# lv_controller.net
KiCad netlist of a schematic drawn in Altium Designer
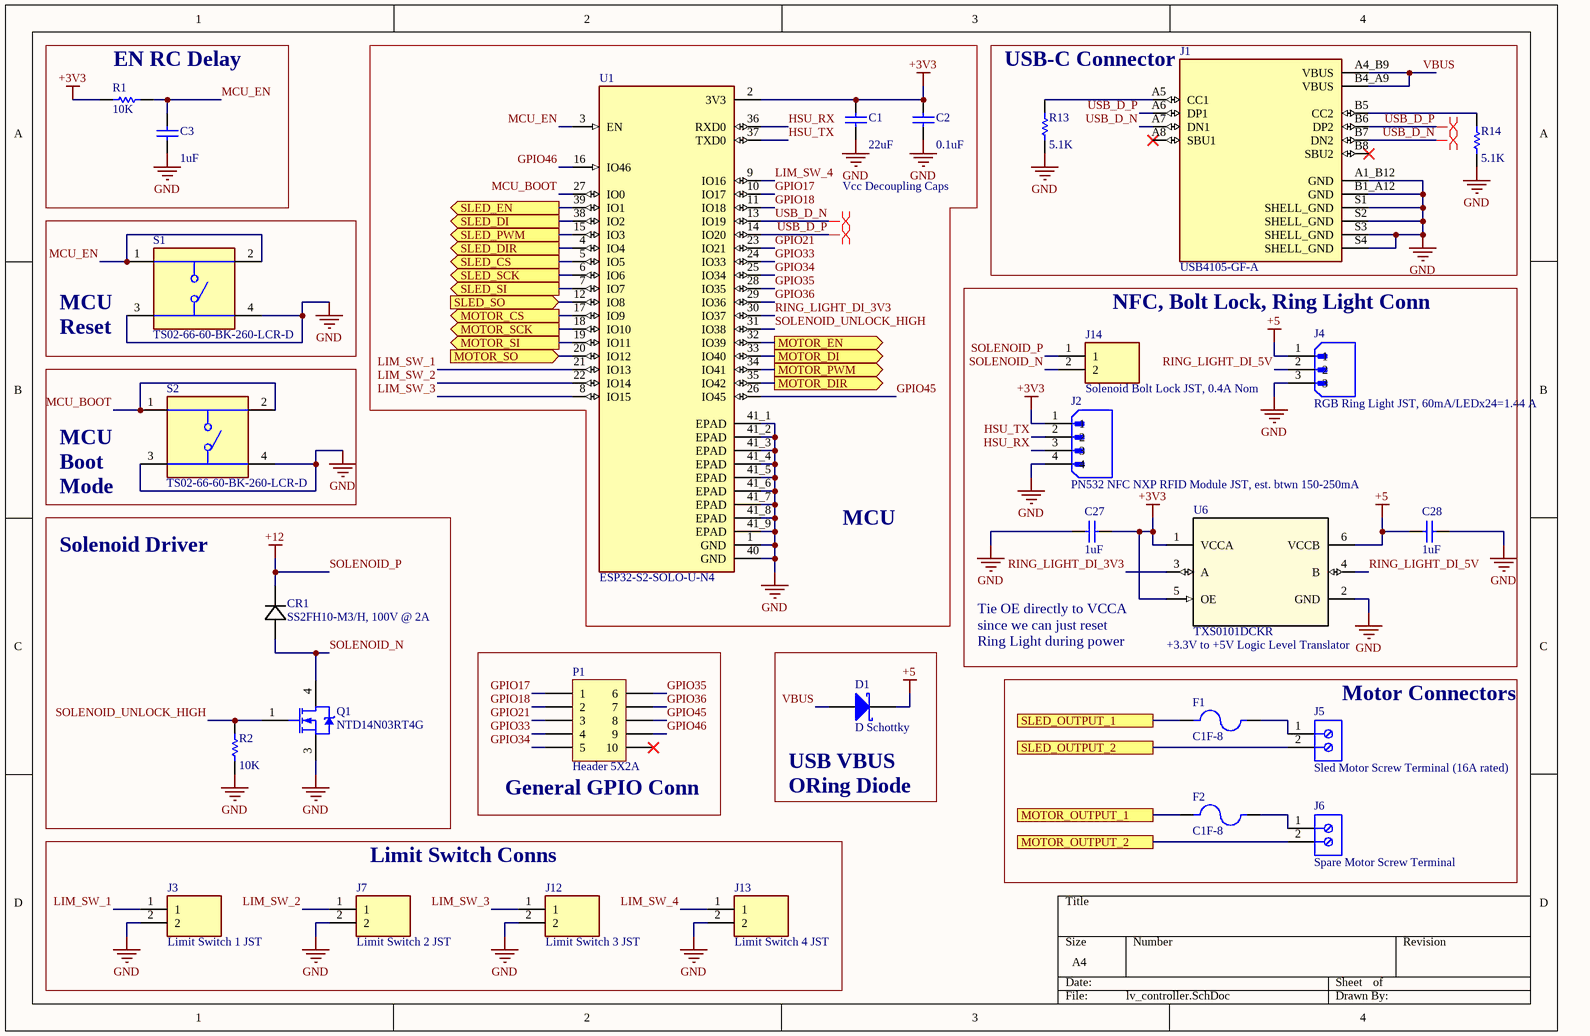
[diagram p0: lv_controller.SchDoc]

(export (version "E")
  (design (tool "Eeschema 10.0.6"))
  (components
    (comp (ref "C1")
      (value "22uF")
      (footprint "C0805")
      (description "Capacitor")
      (fields (field (name "Comment") "Cap") (field (name "PUBLISHER") "Altium Limited"))
      (libsource (lib "Miscellaneous Devices") (part "Cap"))
    )
    (comp (ref "C2")
      (value "0.1uF")
      (footprint "C0805")
      (description "Capacitor")
      (fields (field (name "Comment") "Cap") (field (name "PUBLISHER") "Altium Limited"))
      (libsource (lib "Miscellaneous Devices") (part "Cap"))
    )
    (comp (ref "C3")
      (value "1uF")
      (footprint "C0805")
      (description "Capacitor")
      (fields (field (name "Comment") "Cap") (field (name "PUBLISHER") "Altium Limited"))
      (libsource (lib "Miscellaneous Devices") (part "Cap"))
    )
    (comp (ref "C27")
      (value "1uF")
      (footprint "C0805")
      (description "Capacitor")
      (fields (field (name "Comment") "Cap") (field (name "PUBLISHER") "Altium Limited"))
      (libsource (lib "Miscellaneous Devices") (part "Cap"))
    )
    (comp (ref "C28")
      (value "1uF")
      (footprint "C0805")
      (description "Capacitor")
      (fields (field (name "Comment") "Cap") (field (name "PUBLISHER") "Altium Limited"))
      (libsource (lib "Miscellaneous Devices") (part "Cap"))
    )
    (comp (ref "CR1")
      (value "SS2FH10-M3/H, 100V @ 2A")
      (footprint "CR_10-M3/H_VIS")
      (description "No Description Available")
      (fields
        (field (name "MANUFACTURER_PART_NUMBER") "SS2FH10-M3/H")
        (field (name "COPYRIGHT") "Copyright (C) 2022 Ultra Librarian. All rights reserved.")
      )
      (libsource (lib "lv_controller_lib") (part "SS2FH10-M3/H"))
    )
    (comp (ref "D1")
      (value "D Schottky")
      (footprint "SODFL4725X110N:SODFL4725X110N")
      (description "Schottky Diode")
      (fields (field (name "PUBLISHER") "Altium Limited"))
      (libsource (lib "Miscellaneous Devices") (part "D Schottky"))
    )
    (comp (ref "F1")
      (value "C1F-8")
      (footprint "FUSC3215X83N")
      (description "C1F 8 (0685F8000-01) ¦ 1206 SMT Fuse ¦ Fast Acting ¦ 8A")
      (fields (field (name "MF") "Bel Fuse"))
      (libsource (lib "lv_controller_lib") (part "C1F-8"))
    )
    (comp (ref "F2")
      (value "C1F-8")
      (footprint "FUSC3215X83N")
      (description "C1F 8 (0685F8000-01) ¦ 1206 SMT Fuse ¦ Fast Acting ¦ 8A")
      (fields (field (name "MF") "Bel Fuse"))
      (libsource (lib "lv_controller_lib") (part "C1F-8"))
    )
    (comp (ref "J1")
      (value "USB4105-GF-A")
      (footprint "GCT_USB4105-GF-A")
      (fields (field (name "MF") "GCT"))
      (libsource (lib "lv_controller_lib") (part "USB4105-GF-A"))
    )
    (comp (ref "J2")
      (value "PN532 NFC NXP RFID Module JST, est. btwn 150-250mA")
      (footprint "JST_B4B-XH-A(LF)(SN)")
      (fields (field (name "MP") "B4B-XH-A(LF)(SN)"))
      (libsource (lib "lv_controller_lib") (part "B4B-XH-A(LF)(SN)"))
    )
    (comp (ref "J3")
      (value "Limit Switch 1 JST")
      (footprint "JST_B2B-XH-A(LF)(SN)")
      (description "Connector Header Through Hole 2 position 0.098 (2.50mm)")
      (fields (field (name "MP") "B2B-XH-A(LF)(SN)") (field (name "MF") "JST Sales"))
      (libsource (lib "lv_controller_lib") (part "B2B-XH-A(LF)(SN)"))
    )
    (comp (ref "J4")
      (value "RGB Ring Light JST, 60mA/LEDx24=1.44 A")
      (footprint "JST_B3B-XH-A(LF)(SN)")
      (fields (field (name "MP") "B3B-XH-A(LF)(SN)"))
      (libsource (lib "lv_controller_lib") (part "B3B-XH-A(LF)(SN)"))
    )
    (comp (ref "J5")
      (value "Sled Motor Screw Terminal (16A rated)")
      (footprint "PHOE-1725656-2")
      (description "Male Header, Pitch 2.54 mm, 1 x 2 Position, Height 9 mm, Tail Length 3.5 mm")
      (fields
        (field (name "MANUFACTURER PART NO.") "1725656")
        (field (name "MANUFACTURER") "Phoenix Contact")
      )
      (libsource (lib "Altium Content Vault") (part "CN-1P-F-TB2"))
    )
    (comp (ref "J6")
      (value "Spare Motor Screw Terminal")
      (footprint "PHOE-1725656-2")
      (description "Male Header, Pitch 2.54 mm, 1 x 2 Position, Height 9 mm, Tail Length 3.5 mm")
      (fields
        (field (name "MANUFACTURER PART NO.") "1725656")
        (field (name "MANUFACTURER") "Phoenix Contact")
      )
      (libsource (lib "Altium Content Vault") (part "CN-1P-F-TB2"))
    )
    (comp (ref "J7")
      (value "Limit Switch 2 JST")
      (footprint "JST_B2B-XH-A(LF)(SN)")
      (description "Connector Header Through Hole 2 position 0.098 (2.50mm)")
      (fields (field (name "MP") "B2B-XH-A(LF)(SN)") (field (name "MF") "JST Sales"))
      (libsource (lib "lv_controller_lib") (part "B2B-XH-A(LF)(SN)"))
    )
    (comp (ref "J12")
      (value "Limit Switch 3 JST")
      (footprint "JST_B2B-XH-A(LF)(SN)")
      (description "Connector Header Through Hole 2 position 0.098 (2.50mm)")
      (fields (field (name "MP") "B2B-XH-A(LF)(SN)") (field (name "MF") "JST Sales"))
      (libsource (lib "lv_controller_lib") (part "B2B-XH-A(LF)(SN)"))
    )
    (comp (ref "J13")
      (value "Limit Switch 4 JST")
      (footprint "JST_B2B-XH-A(LF)(SN)")
      (description "Connector Header Through Hole 2 position 0.098 (2.50mm)")
      (fields (field (name "MP") "B2B-XH-A(LF)(SN)") (field (name "MF") "JST Sales"))
      (libsource (lib "lv_controller_lib") (part "B2B-XH-A(LF)(SN)"))
    )
    (comp (ref "J14")
      (value "Solenoid Bolt Lock JST, 0.4A Nom")
      (footprint "JST_B2B-XH-A(LF)(SN)")
      (description "Connector Header Through Hole 2 position 0.098 (2.50mm)")
      (fields (field (name "MP") "B2B-XH-A(LF)(SN)") (field (name "MF") "JST Sales"))
      (libsource (lib "lv_controller_lib") (part "B2B-XH-A(LF)(SN)"))
    )
    (comp (ref "P1")
      (value "Header 5X2A")
      (footprint "HDR2X5_CEN")
      (description "Header, 5-Pin, Dual row")
      (fields (field (name "PUBLISHER") "Altium Limited"))
      (libsource (lib "Miscellaneous Connectors") (part "Header 5X2A"))
    )
    (comp (ref "Q1")
      (value "NTD14N03RT4G")
      (footprint "ONSC-DPAK-3-369C-01_V")
      (description "Power MOSFET, 14 A, 25 V, N-Channel, 3-Pin DPAK, Pb-Free, Tape and Reel")
      (fields (field (name "MANUFACTURER") "On Semiconductor"))
      (libsource (lib "Altium Content Vault") (part "ONSC-NMOS-G1S3D4-3_C"))
    )
    (comp (ref "R1")
      (value "10K")
      (footprint "6-0805_M")
      (description "Resistor")
      (fields (field (name "Comment") "Res1") (field (name "PUBLISHER") "Altium Limited"))
      (libsource (lib "Miscellaneous Devices") (part "Res1"))
    )
    (comp (ref "R2")
      (value "10K")
      (footprint "6-0805_M")
      (description "Resistor")
      (fields (field (name "Comment") "Res1") (field (name "PUBLISHER") "Altium Limited"))
      (libsource (lib "Miscellaneous Devices") (part "Res1"))
    )
    (comp (ref "R13")
      (value "5.1K")
      (footprint "6-0805_M")
      (description "Resistor")
      (fields (field (name "Comment") "Res1") (field (name "PUBLISHER") "Altium Limited"))
      (libsource (lib "Miscellaneous Devices") (part "Res1"))
    )
    (comp (ref "R14")
      (value "5.1K")
      (footprint "6-0805_M")
      (description "Resistor")
      (fields (field (name "Comment") "Res1") (field (name "PUBLISHER") "Altium Limited"))
      (libsource (lib "Miscellaneous Devices") (part "Res1"))
    )
    (comp (ref "S1")
      (value "TS02-66-60-BK-260-LCR-D")
      (footprint "SW_TS02-66-60-BK-260-LCR-D")
      (description "6 x 6 mm, 6 mm Actuator Height, 260 gf, Black, Long Crimped, Through Hole, SPST, Tactile Switch")
      (fields (field (name "MF") "CUI Devices"))
      (libsource (lib "lv_controller_lib") (part "TS02-66-60-BK-260-LCR-D"))
    )
    (comp (ref "S2")
      (value "TS02-66-60-BK-260-LCR-D")
      (footprint "SW_TS02-66-60-BK-260-LCR-D")
      (description "6 x 6 mm, 6 mm Actuator Height, 260 gf, Black, Long Crimped, Through Hole, SPST, Tactile Switch")
      (fields (field (name "MF") "CUI Devices"))
      (libsource (lib "lv_controller_lib") (part "TS02-66-60-BK-260-LCR-D"))
    )
    (comp (ref "U1")
      (value "ESP32-S2-SOLO-U-N4")
      (footprint "XCVR_ESP32-S2-SOLO-U-N4R2:XCVR_ESP32-S2-SOLO-U-N4R2")
      (description "WiFi 802.11b/g/n Transceiver Module 2.4GHz PCB Trace + IPEX Surface Mount")
      (fields (field (name "MP") "ESP32-S2-SOLO-U-N4R2") (field (name "MF") "Espressif Systems"))
      (libsource (lib "ESP32-S2-SOLO-U-N4R2") (part "ESP32-S2-SOLO-U-N4R2"))
    )
    (comp (ref "U6")
      (value "TXS0101DCKR")
      (footprint "DCK0006A_N")
      (description "No Description Available")
      (fields (field (name "COPYRIGHT") "Copyright (C) 2022 Ultra Librarian. All rights reserved."))
      (libsource (lib "lv_controller_lib") (part "TXS0101DCKR"))
    )
  )
  (nets
    (net (code "1") (name "+3V3") (class "Default")
      (node (ref "C1") (pin "2") (pinfunction "2_2") (pintype "passive"))
      (node (ref "C2") (pin "2") (pinfunction "2_2") (pintype "passive"))
      (node (ref "C27") (pin "1") (pinfunction "1_1") (pintype "passive"))
      (node (ref "J2") (pin "1") (pinfunction "1_1") (pintype "passive"))
      (node (ref "R1") (pin "1") (pinfunction "1_1") (pintype "passive"))
      (node (ref "U1") (pin "2") (pinfunction "3V3_2") (pintype "power_in"))
      (node (ref "U6") (pin "1") (pinfunction "VCCA_1") (pintype "power_in"))
      (node (ref "U6") (pin "5") (pinfunction "OE_5") (pintype "input"))
    )
    (net (code "2") (name "+5") (class "Default")
      (node (ref "C28") (pin "2") (pinfunction "2_2") (pintype "passive"))
      (node (ref "D1") (pin "2") (pinfunction "K_2") (pintype "passive"))
      (node (ref "J4") (pin "1") (pinfunction "1_1") (pintype "passive"))
      (node (ref "U6") (pin "6") (pinfunction "VCCB_6") (pintype "power_in"))
    )
    (net (code "3") (name "+12") (class "Default")
      (node (ref "CR1") (pin "1") (pinfunction "1_1") (pintype "passive"))
      (node (ref "J14") (pin "1") (pinfunction "1_1") (pintype "passive"))
    )
    (net (code "4") (name "/GPIO17") (class "Default")
      (node (ref "P1") (pin "1") (pinfunction "1_1") (pintype "passive"))
      (node (ref "U1") (pin "10") (pinfunction "IO17_10") (pintype "bidirectional"))
    )
    (net (code "5") (name "/GPIO18") (class "Default")
      (node (ref "P1") (pin "2") (pinfunction "2_2") (pintype "passive"))
      (node (ref "U1") (pin "11") (pinfunction "IO18_11") (pintype "bidirectional"))
    )
    (net (code "6") (name "/GPIO21") (class "Default")
      (node (ref "P1") (pin "3") (pinfunction "3_3") (pintype "passive"))
      (node (ref "U1") (pin "23") (pinfunction "IO21_23") (pintype "bidirectional"))
    )
    (net (code "7") (name "/GPIO33") (class "Default")
      (node (ref "P1") (pin "4") (pinfunction "4_4") (pintype "passive"))
      (node (ref "U1") (pin "24") (pinfunction "IO33_24") (pintype "bidirectional"))
    )
    (net (code "8") (name "/GPIO34") (class "Default")
      (node (ref "P1") (pin "5") (pinfunction "5_5") (pintype "passive"))
      (node (ref "U1") (pin "25") (pinfunction "IO34_25") (pintype "bidirectional"))
    )
    (net (code "9") (name "/GPIO35") (class "Default")
      (node (ref "P1") (pin "6") (pinfunction "6_6") (pintype "passive"))
      (node (ref "U1") (pin "28") (pinfunction "IO35_28") (pintype "bidirectional"))
    )
    (net (code "10") (name "/GPIO36") (class "Default")
      (node (ref "P1") (pin "7") (pinfunction "7_7") (pintype "passive"))
      (node (ref "U1") (pin "29") (pinfunction "IO36_29") (pintype "bidirectional"))
    )
    (net (code "11") (name "/GPIO45") (class "Default")
      (node (ref "P1") (pin "8") (pinfunction "8_8") (pintype "passive"))
      (node (ref "U1") (pin "26") (pinfunction "IO45_26") (pintype "bidirectional"))
    )
    (net (code "12") (name "/GPIO46") (class "Default")
      (node (ref "P1") (pin "9") (pinfunction "9_9") (pintype "passive"))
      (node (ref "U1") (pin "16") (pinfunction "IO46_16") (pintype "input"))
    )
    (net (code "13") (name "/HSU_RX") (class "Default")
      (node (ref "J2") (pin "3") (pinfunction "3_3") (pintype "passive"))
      (node (ref "U1") (pin "36") (pinfunction "RXD0_36") (pintype "bidirectional"))
    )
    (net (code "14") (name "/HSU_TX") (class "Default")
      (node (ref "J2") (pin "2") (pinfunction "2_2") (pintype "passive"))
      (node (ref "U1") (pin "37") (pinfunction "TXD0_37") (pintype "bidirectional"))
    )
    (net (code "15") (name "/LIM_SW_1") (class "Default")
      (node (ref "J3") (pin "1") (pinfunction "1_1") (pintype "passive"))
      (node (ref "U1") (pin "21") (pinfunction "IO13_21") (pintype "bidirectional"))
    )
    (net (code "16") (name "/LIM_SW_2") (class "Default")
      (node (ref "J7") (pin "1") (pinfunction "1_1") (pintype "passive"))
      (node (ref "U1") (pin "22") (pinfunction "IO14_22") (pintype "bidirectional"))
    )
    (net (code "17") (name "/LIM_SW_3") (class "Default")
      (node (ref "J12") (pin "1") (pinfunction "1_1") (pintype "passive"))
      (node (ref "U1") (pin "8") (pinfunction "IO15_8") (pintype "bidirectional"))
    )
    (net (code "18") (name "/LIM_SW_4") (class "Default")
      (node (ref "J13") (pin "1") (pinfunction "1_1") (pintype "passive"))
      (node (ref "U1") (pin "9") (pinfunction "IO16_9") (pintype "bidirectional"))
    )
    (net (code "19") (name "/MCU_BOOT") (class "Default")
      (node (ref "S2") (pin "1") (pinfunction "1_1") (pintype "passive"))
      (node (ref "S2") (pin "2") (pinfunction "2_2") (pintype "passive"))
      (node (ref "U1") (pin "27") (pinfunction "IO0_27") (pintype "bidirectional"))
    )
    (net (code "20") (name "/MCU_EN") (class "Default")
      (node (ref "C3") (pin "2") (pinfunction "2_2") (pintype "passive"))
      (node (ref "R1") (pin "2") (pinfunction "2_2") (pintype "passive"))
      (node (ref "S1") (pin "1") (pinfunction "1_1") (pintype "passive"))
      (node (ref "S1") (pin "2") (pinfunction "2_2") (pintype "passive"))
      (node (ref "U1") (pin "3") (pinfunction "EN_3") (pintype "input"))
    )
    (net (code "21") (name "/MOTOR_CS") (class "Default")
      (node (ref "U1") (pin "17") (pinfunction "IO9_17") (pintype "bidirectional"))
    )
    (net (code "22") (name "/MOTOR_DI") (class "Default")
      (node (ref "U1") (pin "33") (pinfunction "IO40_33") (pintype "bidirectional"))
    )
    (net (code "23") (name "/MOTOR_DIR") (class "Default")
      (node (ref "U1") (pin "35") (pinfunction "IO42_35") (pintype "bidirectional"))
    )
    (net (code "24") (name "/MOTOR_EN") (class "Default")
      (node (ref "U1") (pin "32") (pinfunction "IO39_32") (pintype "bidirectional"))
    )
    (net (code "25") (name "/MOTOR_OUTPUT_1") (class "Default")
      (node (ref "F2") (pin "1") (pinfunction "1_1") (pintype "passive"))
    )
    (net (code "26") (name "/MOTOR_OUTPUT_2") (class "Default")
      (node (ref "J6") (pin "2") (pinfunction "2_2") (pintype "passive"))
    )
    (net (code "27") (name "/MOTOR_PWM") (class "Default")
      (node (ref "U1") (pin "34") (pinfunction "IO41_34") (pintype "bidirectional"))
    )
    (net (code "28") (name "/MOTOR_SCK") (class "Default")
      (node (ref "U1") (pin "18") (pinfunction "IO10_18") (pintype "bidirectional"))
    )
    (net (code "29") (name "/MOTOR_SI") (class "Default")
      (node (ref "U1") (pin "19") (pinfunction "IO11_19") (pintype "bidirectional"))
    )
    (net (code "30") (name "/MOTOR_SO") (class "Default")
      (node (ref "U1") (pin "20") (pinfunction "IO12_20") (pintype "bidirectional"))
    )
    (net (code "31") (name "/RING_LIGHT_DI_3V3") (class "Default")
      (node (ref "U1") (pin "30") (pinfunction "IO37_30") (pintype "bidirectional"))
      (node (ref "U6") (pin "3") (pinfunction "A_3") (pintype "bidirectional"))
    )
    (net (code "32") (name "/RING_LIGHT_DI_5V") (class "Default")
      (node (ref "J4") (pin "2") (pinfunction "2_2") (pintype "passive"))
      (node (ref "U6") (pin "4") (pinfunction "B_4") (pintype "bidirectional"))
    )
    (net (code "33") (name "/SLED_CS") (class "Default")
      (node (ref "U1") (pin "5") (pinfunction "IO5_5") (pintype "bidirectional"))
    )
    (net (code "34") (name "/SLED_DI") (class "Default")
      (node (ref "U1") (pin "38") (pinfunction "IO2_38") (pintype "bidirectional"))
    )
    (net (code "35") (name "/SLED_DIR") (class "Default")
      (node (ref "U1") (pin "4") (pinfunction "IO4_4") (pintype "bidirectional"))
    )
    (net (code "36") (name "/SLED_EN") (class "Default")
      (node (ref "U1") (pin "39") (pinfunction "IO1_39") (pintype "bidirectional"))
    )
    (net (code "37") (name "/SLED_OUTPUT_1") (class "Default")
      (node (ref "F1") (pin "1") (pinfunction "1_1") (pintype "passive"))
    )
    (net (code "38") (name "/SLED_OUTPUT_2") (class "Default")
      (node (ref "J5") (pin "2") (pinfunction "2_2") (pintype "passive"))
    )
    (net (code "39") (name "/SLED_PWM") (class "Default")
      (node (ref "U1") (pin "15") (pinfunction "IO3_15") (pintype "bidirectional"))
    )
    (net (code "40") (name "/SLED_SCK") (class "Default")
      (node (ref "U1") (pin "6") (pinfunction "IO6_6") (pintype "bidirectional"))
    )
    (net (code "41") (name "/SLED_SI") (class "Default")
      (node (ref "U1") (pin "7") (pinfunction "IO7_7") (pintype "bidirectional"))
    )
    (net (code "42") (name "/SLED_SO") (class "Default")
      (node (ref "U1") (pin "12") (pinfunction "IO8_12") (pintype "bidirectional"))
    )
    (net (code "43") (name "/SOLENOID_N") (class "Default")
      (node (ref "CR1") (pin "2") (pinfunction "2_2") (pintype "passive"))
      (node (ref "J14") (pin "2") (pinfunction "2_2") (pintype "passive"))
      (node (ref "Q1") (pin "4") (pinfunction "D_4") (pintype "passive"))
    )
    (net (code "44") (name "/SOLENOID_UNLOCK_HIGH") (class "Default")
      (node (ref "Q1") (pin "1") (pinfunction "G_1") (pintype "passive"))
      (node (ref "R2") (pin "1") (pinfunction "1_1") (pintype "passive"))
      (node (ref "U1") (pin "31") (pinfunction "IO38_31") (pintype "bidirectional"))
    )
    (net (code "45") (name "/USB_D_N") (class "Default")
      (node (ref "J1") (pin "A7") (pinfunction "DN1_A7") (pintype "bidirectional"))
      (node (ref "J1") (pin "B7") (pinfunction "DN2_B7") (pintype "bidirectional"))
      (node (ref "U1") (pin "13") (pinfunction "IO19_13") (pintype "bidirectional"))
    )
    (net (code "46") (name "/USB_D_P") (class "Default")
      (node (ref "J1") (pin "A6") (pinfunction "DP1_A6") (pintype "bidirectional"))
      (node (ref "J1") (pin "B6") (pinfunction "DP2_B6") (pintype "bidirectional"))
      (node (ref "U1") (pin "14") (pinfunction "IO20_14") (pintype "bidirectional"))
    )
    (net (code "47") (name "/VBUS") (class "Default")
      (node (ref "D1") (pin "1") (pinfunction "A_1") (pintype "passive"))
      (node (ref "J1") (pin "A4_B9") (pinfunction "VBUS_A4_B9") (pintype "power_in"))
      (node (ref "J1") (pin "B4_A9") (pinfunction "VBUS_B4_A9") (pintype "power_in"))
    )
    (net (code "48") (name "GND") (class "Default")
      (node (ref "C1") (pin "1") (pinfunction "1_1") (pintype "passive"))
      (node (ref "C2") (pin "1") (pinfunction "1_1") (pintype "passive"))
      (node (ref "C27") (pin "2") (pinfunction "2_2") (pintype "passive"))
      (node (ref "C28") (pin "1") (pinfunction "1_1") (pintype "passive"))
      (node (ref "C3") (pin "1") (pinfunction "1_1") (pintype "passive"))
      (node (ref "J1") (pin "A1_B12") (pinfunction "GND_A1_B12") (pintype "power_in"))
      (node (ref "J1") (pin "B1_A12") (pinfunction "GND_B1_A12") (pintype "power_in"))
      (node (ref "J1") (pin "S1") (pinfunction "SHELL_GND_S1") (pintype "power_in"))
      (node (ref "J1") (pin "S2") (pinfunction "SHELL_GND_S2") (pintype "power_in"))
      (node (ref "J1") (pin "S3") (pinfunction "SHELL_GND_S3") (pintype "power_in"))
      (node (ref "J1") (pin "S4") (pinfunction "SHELL_GND_S4") (pintype "power_in"))
      (node (ref "J12") (pin "2") (pinfunction "2_2") (pintype "passive"))
      (node (ref "J13") (pin "2") (pinfunction "2_2") (pintype "passive"))
      (node (ref "J2") (pin "4") (pinfunction "4_4") (pintype "passive"))
      (node (ref "J3") (pin "2") (pinfunction "2_2") (pintype "passive"))
      (node (ref "J4") (pin "3") (pinfunction "3_3") (pintype "passive"))
      (node (ref "J7") (pin "2") (pinfunction "2_2") (pintype "passive"))
      (node (ref "Q1") (pin "3") (pinfunction "S_3") (pintype "passive"))
      (node (ref "R13") (pin "1") (pinfunction "1_1") (pintype "passive"))
      (node (ref "R14") (pin "1") (pinfunction "1_1") (pintype "passive"))
      (node (ref "R2") (pin "2") (pinfunction "2_2") (pintype "passive"))
      (node (ref "S1") (pin "3") (pinfunction "3_3") (pintype "passive"))
      (node (ref "S1") (pin "4") (pinfunction "4_4") (pintype "passive"))
      (node (ref "S2") (pin "3") (pinfunction "3_3") (pintype "passive"))
      (node (ref "S2") (pin "4") (pinfunction "4_4") (pintype "passive"))
      (node (ref "U1") (pin "1") (pinfunction "GND_1") (pintype "power_in"))
      (node (ref "U1") (pin "40") (pinfunction "GND_40") (pintype "power_in"))
      (node (ref "U1") (pin "41_1") (pinfunction "EPAD_41_1") (pintype "power_in"))
      (node (ref "U1") (pin "41_2") (pinfunction "EPAD_41_2") (pintype "power_in"))
      (node (ref "U1") (pin "41_3") (pinfunction "EPAD_41_3") (pintype "power_in"))
      (node (ref "U1") (pin "41_4") (pinfunction "EPAD_41_4") (pintype "power_in"))
      (node (ref "U1") (pin "41_5") (pinfunction "EPAD_41_5") (pintype "power_in"))
      (node (ref "U1") (pin "41_6") (pinfunction "EPAD_41_6") (pintype "power_in"))
      (node (ref "U1") (pin "41_7") (pinfunction "EPAD_41_7") (pintype "power_in"))
      (node (ref "U1") (pin "41_8") (pinfunction "EPAD_41_8") (pintype "power_in"))
      (node (ref "U1") (pin "41_9") (pinfunction "EPAD_41_9") (pintype "power_in"))
      (node (ref "U6") (pin "2") (pinfunction "GND_2") (pintype "power_in"))
    )
    (net (code "49") (name "Net-(F1-Pad2)") (class "Default")
      (node (ref "F1") (pin "2") (pinfunction "2_2") (pintype "passive"))
      (node (ref "J5") (pin "1") (pinfunction "1_1") (pintype "passive"))
    )
    (net (code "50") (name "Net-(F2-Pad2)") (class "Default")
      (node (ref "F2") (pin "2") (pinfunction "2_2") (pintype "passive"))
      (node (ref "J6") (pin "1") (pinfunction "1_1") (pintype "passive"))
    )
    (net (code "51") (name "Net-(J1-CC1)") (class "Default")
      (node (ref "J1") (pin "A5") (pinfunction "CC1_A5") (pintype "bidirectional"))
      (node (ref "R13") (pin "2") (pinfunction "2_2") (pintype "passive"))
    )
    (net (code "52") (name "Net-(J1-CC2)") (class "Default")
      (node (ref "J1") (pin "B5") (pinfunction "CC2_B5") (pintype "bidirectional"))
      (node (ref "R14") (pin "2") (pinfunction "2_2") (pintype "passive"))
    )
    (net (code "53") (name "unconnected-(J1-SBU1-PadA8)") (class "Default")
      (node (ref "J1") (pin "A8") (pinfunction "SBU1_A8") (pintype "bidirectional+no_connect"))
    )
    (net (code "54") (name "unconnected-(J1-SBU2-PadB8)") (class "Default")
      (node (ref "J1") (pin "B8") (pinfunction "SBU2_B8") (pintype "bidirectional+no_connect"))
    )
    (net (code "55") (name "unconnected-(P1-Pad10)") (class "Default")
      (node (ref "P1") (pin "10") (pinfunction "10_10") (pintype "passive+no_connect"))
    )
  )
)
